# dev-test.net
KiCad netlist of a schematic drawn in EAGLE
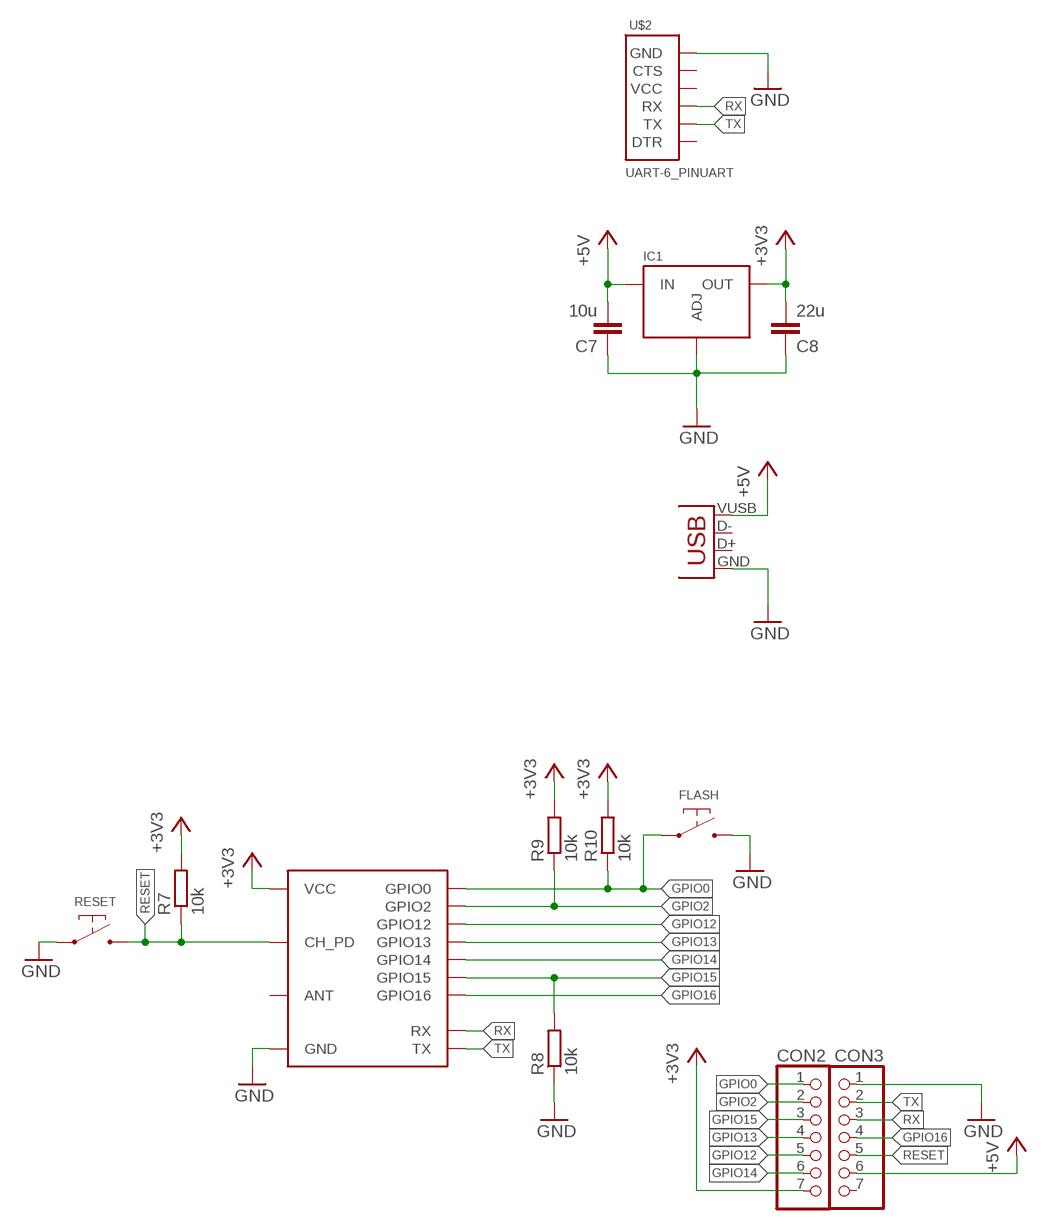
[diagram p0: schematic, sheet 1]

(export (version "E")
  (design (tool "Eeschema 10.0.6"))
  (components
    (comp (ref "C7")
      (value "10u")
      (footprint "eagle-import:C0805")
      (libsource (lib "eagle-import") (part "C-EUC0805"))
    )
    (comp (ref "C8")
      (value "22u")
      (footprint "eagle-import:C0805")
      (libsource (lib "eagle-import") (part "C-EUC0805"))
    )
    (comp (ref "CON1")
      (value "USBMICRO-NO_CENTER")
      (footprint "eagle-import:USB-MICRO-SMD-NO_CENTER")
      (libsource (lib "eagle-import") (part "USBMICRO-NO_CENTER"))
    )
    (comp (ref "CON2")
      (value "GENERIC-1X7THT")
      (footprint "eagle-import:PINHEADER-100MIL-1X7")
      (libsource (lib "eagle-import") (part "GENERIC-1X7THT"))
    )
    (comp (ref "CON3")
      (value "GENERIC-1X7THT")
      (footprint "eagle-import:PINHEADER-100MIL-1X7")
      (libsource (lib "eagle-import") (part "GENERIC-1X7THT"))
    )
    (comp (ref "FLASH")
      (value "SWITCH-DEFAULT_OFF-SMD-2_PIN")
      (footprint "eagle-import:SWITCH-SMD-2_PIN-DX")
      (libsource (lib "eagle-import") (part "SWITCH-DEFAULT_OFF-SMD-2_PIN"))
    )
    (comp (ref "IC1")
      (value "REGULATOR-LM317-SOT223")
      (footprint "eagle-import:SOT223")
      (libsource (lib "eagle-import") (part "REGULATOR-LM317-SOT223"))
    )
    (comp (ref "R7")
      (value "10k")
      (footprint "eagle-import:R0603")
      (libsource (lib "eagle-import") (part "R-EU_R0603"))
    )
    (comp (ref "R8")
      (value "10k")
      (footprint "eagle-import:R0603")
      (libsource (lib "eagle-import") (part "R-EU_R0603"))
    )
    (comp (ref "R9")
      (value "10k")
      (footprint "eagle-import:R0603")
      (libsource (lib "eagle-import") (part "R-EU_R0603"))
    )
    (comp (ref "R10")
      (value "10k")
      (footprint "eagle-import:R0603")
      (libsource (lib "eagle-import") (part "R-EU_R0603"))
    )
    (comp (ref "RESET")
      (value "SWITCH-DEFAULT_OFF-SMD-2_PIN")
      (footprint "eagle-import:SWITCH-SMD-2_PIN-DX")
      (libsource (lib "eagle-import") (part "SWITCH-DEFAULT_OFF-SMD-2_PIN"))
    )
    (comp (ref "U$1")
      (value "ESP8266-03")
      (footprint "eagle-import:ESP8266-ESP-03")
      (libsource (lib "eagle-import") (part "ESP8266-03"))
    )
    (comp (ref "U$2")
      (value "UART-6_PINUART")
      (footprint "eagle-import:ANGLE-1X6")
      (libsource (lib "eagle-import") (part "UART-6_PINUART"))
    )
  )
  (nets
    (net (code "1") (name "+3V3") (class "Default")
      (node (ref "C8") (pin "2") (pinfunction "2_2") (pintype "passive"))
      (node (ref "CON2") (pin "7") (pinfunction "7_7") (pintype "passive"))
      (node (ref "IC1") (pin "2") (pinfunction "OUT_2") (pintype "bidirectional"))
      (node (ref "IC1") (pin "4") (pinfunction "OUT_4") (pintype "bidirectional"))
      (node (ref "R10") (pin "2") (pinfunction "2_2") (pintype "passive"))
      (node (ref "R7") (pin "2") (pinfunction "2_2") (pintype "passive"))
      (node (ref "R9") (pin "2") (pinfunction "2_2") (pintype "passive"))
      (node (ref "U$1") (pin "P$8") (pinfunction "VCC_P$8") (pintype "bidirectional"))
    )
    (net (code "2") (name "+5V") (class "Default")
      (node (ref "C7") (pin "2") (pinfunction "2_2") (pintype "passive"))
      (node (ref "CON1") (pin "VUSB") (pinfunction "VBUS_VUSB") (pintype "bidirectional"))
      (node (ref "CON3") (pin "6") (pinfunction "6_6") (pintype "passive"))
      (node (ref "IC1") (pin "3") (pinfunction "IN_3") (pintype "bidirectional"))
    )
    (net (code "3") (name "GND") (class "Default")
      (node (ref "C7") (pin "1") (pinfunction "1_1") (pintype "passive"))
      (node (ref "C8") (pin "1") (pinfunction "1_1") (pintype "passive"))
      (node (ref "CON1") (pin "GND") (pinfunction "GND_GND") (pintype "bidirectional"))
      (node (ref "CON3") (pin "1") (pinfunction "1_1") (pintype "passive"))
      (node (ref "FLASH") (pin "P$2") (pinfunction "P$2_P$2") (pintype "bidirectional"))
      (node (ref "IC1") (pin "1") (pinfunction "ADJ_1") (pintype "bidirectional"))
      (node (ref "R8") (pin "1") (pinfunction "1_1") (pintype "passive"))
      (node (ref "RESET") (pin "P$1") (pinfunction "P$1_P$1") (pintype "bidirectional"))
      (node (ref "U$1") (pin "P$1") (pinfunction "GND_P$1") (pintype "bidirectional"))
      (node (ref "U$2") (pin "1") (pinfunction "GND_1") (pintype "bidirectional"))
    )
    (net (code "4") (name "GPIO0") (class "Default")
      (node (ref "CON2") (pin "1") (pinfunction "1_1") (pintype "passive"))
      (node (ref "FLASH") (pin "P$1") (pinfunction "P$1_P$1") (pintype "bidirectional"))
      (node (ref "R10") (pin "1") (pinfunction "1_1") (pintype "passive"))
      (node (ref "U$1") (pin "P$14") (pinfunction "GPIO0_P$14") (pintype "bidirectional"))
    )
    (net (code "5") (name "GPIO2") (class "Default")
      (node (ref "CON2") (pin "2") (pinfunction "2_2") (pintype "passive"))
      (node (ref "R9") (pin "1") (pinfunction "1_1") (pintype "passive"))
      (node (ref "U$1") (pin "P$13") (pinfunction "GPIO2_P$13") (pintype "bidirectional"))
    )
    (net (code "6") (name "GPIO12") (class "Default")
      (node (ref "CON2") (pin "5") (pinfunction "5_5") (pintype "passive"))
      (node (ref "U$1") (pin "P$10") (pinfunction "GPIO12_P$10") (pintype "bidirectional"))
    )
    (net (code "7") (name "GPIO13") (class "Default")
      (node (ref "CON2") (pin "4") (pinfunction "4_4") (pintype "passive"))
      (node (ref "U$1") (pin "P$11") (pinfunction "GPIO13_P$11") (pintype "bidirectional"))
    )
    (net (code "8") (name "GPIO14") (class "Default")
      (node (ref "CON2") (pin "6") (pinfunction "6_6") (pintype "passive"))
      (node (ref "U$1") (pin "P$9") (pinfunction "GPIO14_P$9") (pintype "bidirectional"))
    )
    (net (code "9") (name "GPIO15") (class "Default")
      (node (ref "CON2") (pin "3") (pinfunction "3_3") (pintype "passive"))
      (node (ref "R8") (pin "2") (pinfunction "2_2") (pintype "passive"))
      (node (ref "U$1") (pin "P$12") (pinfunction "GPIO15_P$12") (pintype "bidirectional"))
    )
    (net (code "10") (name "GPIO16") (class "Default")
      (node (ref "CON3") (pin "4") (pinfunction "4_4") (pintype "passive"))
      (node (ref "U$1") (pin "P$5") (pinfunction "GPIO16_P$5") (pintype "bidirectional"))
    )
    (net (code "11") (name "RESET") (class "Default")
      (node (ref "CON3") (pin "5") (pinfunction "5_5") (pintype "passive"))
      (node (ref "R7") (pin "1") (pinfunction "1_1") (pintype "passive"))
      (node (ref "RESET") (pin "P$2") (pinfunction "P$2_P$2") (pintype "bidirectional"))
      (node (ref "U$1") (pin "P$6") (pinfunction "CH_PD_P$6") (pintype "bidirectional"))
    )
    (net (code "12") (name "RX") (class "Default")
      (node (ref "CON3") (pin "3") (pinfunction "3_3") (pintype "passive"))
      (node (ref "U$1") (pin "P$4") (pinfunction "RX_P$4") (pintype "bidirectional"))
      (node (ref "U$2") (pin "4") (pinfunction "RX_4") (pintype "bidirectional"))
    )
    (net (code "13") (name "TX") (class "Default")
      (node (ref "CON3") (pin "2") (pinfunction "2_2") (pintype "passive"))
      (node (ref "U$1") (pin "P$3") (pinfunction "TX_P$3") (pintype "bidirectional"))
      (node (ref "U$2") (pin "5") (pinfunction "TX_5") (pintype "bidirectional"))
    )
    (net (code "14") (name "unconnected-(CON1-PadD+)") (class "Default")
      (node (ref "CON1") (pin "D+") (pinfunction "D+_D+") (pintype "bidirectional"))
    )
    (net (code "15") (name "unconnected-(CON1-PadD-)") (class "Default")
      (node (ref "CON1") (pin "D-") (pinfunction "D-_D-") (pintype "bidirectional"))
    )
    (net (code "16") (name "unconnected-(CON3-Pad7)") (class "Default")
      (node (ref "CON3") (pin "7") (pinfunction "7_7") (pintype "passive"))
    )
    (net (code "17") (name "unconnected-(U$1-ANT-PadP$7)") (class "Default")
      (node (ref "U$1") (pin "P$7") (pinfunction "ANT_P$7") (pintype "bidirectional"))
    )
    (net (code "18") (name "unconnected-(U$2-CTS-Pad2)") (class "Default")
      (node (ref "U$2") (pin "2") (pinfunction "CTS_2") (pintype "bidirectional"))
    )
    (net (code "19") (name "unconnected-(U$2-DTR-Pad6)") (class "Default")
      (node (ref "U$2") (pin "6") (pinfunction "DTR_6") (pintype "bidirectional"))
    )
    (net (code "20") (name "unconnected-(U$2-VCC-Pad3)") (class "Default")
      (node (ref "U$2") (pin "3") (pinfunction "VCC_3") (pintype "bidirectional"))
    )
  )
)
